# Brians_test_board_1_17.net
KiCad netlist of a schematic drawn in EAGLE
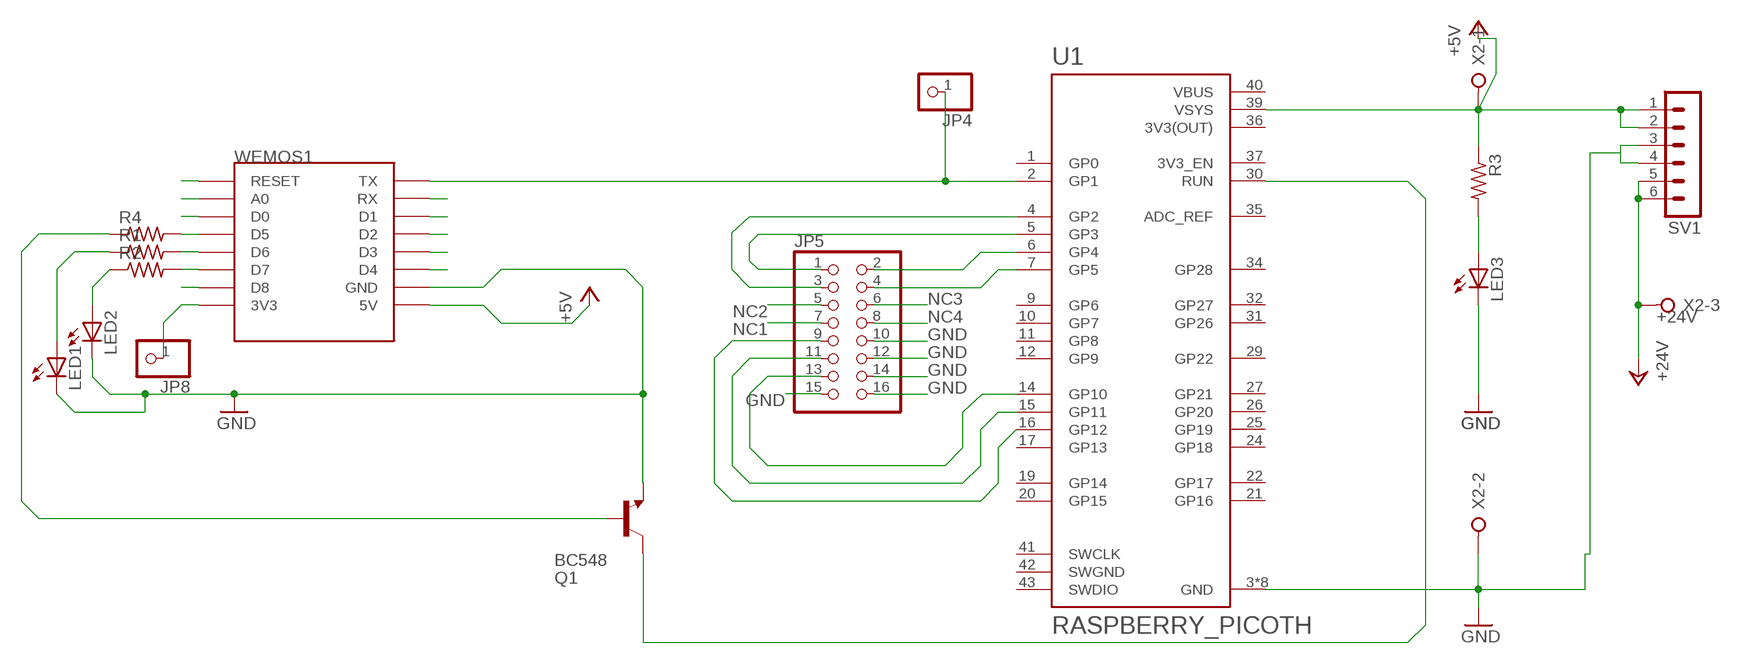
[diagram p0: schematic, sheet 1]

(export (version "E")
  (design (tool "Eeschema 10.0.6"))
  (components
    (comp (ref "JP4")
      (value "PINHD-1X1")
      (footprint "eagle-import:1X01")
      (libsource (lib "eagle-import") (part "PINHD-1X1"))
    )
    (comp (ref "JP5")
      (value "PINHD-2X8")
      (footprint "eagle-import:2X08")
      (libsource (lib "eagle-import") (part "PINHD-2X8"))
    )
    (comp (ref "JP8")
      (value "PINHD-1X1")
      (footprint "eagle-import:1X01")
      (libsource (lib "eagle-import") (part "PINHD-1X1"))
    )
    (comp (ref "LED1")
      (value "LED3MM")
      (footprint "eagle-import:LED3MM")
      (libsource (lib "eagle-import") (part "LED3MM"))
    )
    (comp (ref "LED2")
      (value "LED3MM")
      (footprint "eagle-import:LED3MM")
      (libsource (lib "eagle-import") (part "LED3MM"))
    )
    (comp (ref "LED3")
      (value "LED3MM")
      (footprint "eagle-import:LED3MM")
      (libsource (lib "eagle-import") (part "LED3MM"))
    )
    (comp (ref "Q1")
      (value "BC548")
      (footprint "eagle-import:TO92-EBC")
      (libsource (lib "eagle-import") (part "BC548"))
    )
    (comp (ref "R1")
      (value "R-US_0204/2V")
      (footprint "eagle-import:0204V")
      (libsource (lib "eagle-import") (part "R-US_0204/2V"))
    )
    (comp (ref "R2")
      (value "R-US_0204/2V")
      (footprint "eagle-import:0204V")
      (libsource (lib "eagle-import") (part "R-US_0204/2V"))
    )
    (comp (ref "R3")
      (value "R-US_0207/10")
      (footprint "eagle-import:0207_10")
      (libsource (lib "eagle-import") (part "R-US_0207/10"))
    )
    (comp (ref "R4")
      (value "R-US_0204/2V")
      (footprint "eagle-import:0204V")
      (libsource (lib "eagle-import") (part "R-US_0204/2V"))
    )
    (comp (ref "SV1")
      (value "MA06-1")
      (footprint "eagle-import:MA06-1")
      (libsource (lib "eagle-import") (part "MA06-1"))
    )
    (comp (ref "U1")
      (value "RASPBERRY_PICOTH")
      (footprint "eagle-import:PICO-PKG-TH")
      (libsource (lib "eagle-import") (part "RASPBERRY_PICOTH"))
    )
    (comp (ref "WEMOS1")
      (value "WEMOS-D1-MINI")
      (footprint "eagle-import:WEMOS-D1-MINI")
      (libsource (lib "eagle-import") (part "WEMOS-D1-MINI"))
    )
    (comp (ref "X2")
      (value "W237-3E")
      (footprint "eagle-import:W237-3E")
      (libsource (lib "eagle-import") (part "W237-3E"))
    )
  )
  (nets
    (net (code "1") (name "+5V") (class "Default")
      (node (ref "R3") (pin "1") (pinfunction "1_1") (pintype "passive"))
      (node (ref "SV1") (pin "1") (pinfunction "1_1") (pintype "passive"))
      (node (ref "SV1") (pin "2") (pinfunction "2_2") (pintype "passive"))
      (node (ref "U1") (pin "39") (pinfunction "VSYS_39") (pintype "power_in"))
      (node (ref "WEMOS1") (pin "5V") (pinfunction "5V_5V") (pintype "bidirectional"))
      (node (ref "X2") (pin "1") (pinfunction "KL_1") (pintype "passive"))
    )
    (net (code "2") (name "+24V") (class "Default")
      (node (ref "SV1") (pin "5") (pinfunction "5_5") (pintype "passive"))
      (node (ref "SV1") (pin "6") (pinfunction "6_6") (pintype "passive"))
      (node (ref "X2") (pin "3") (pinfunction "KL_3") (pintype "passive"))
    )
    (net (code "3") (name "/3V3(OUT)") (class "Default")
      (node (ref "U1") (pin "36") (pinfunction "3V3(OUT)_36") (pintype "power_in"))
    )
    (net (code "4") (name "/NC1") (class "Default")
      (node (ref "JP5") (pin "7") (pinfunction "7_7") (pintype "passive"))
    )
    (net (code "5") (name "/NC2") (class "Default")
      (node (ref "JP5") (pin "5") (pinfunction "5_5") (pintype "passive"))
    )
    (net (code "6") (name "/NC3") (class "Default")
      (node (ref "JP5") (pin "6") (pinfunction "6_6") (pintype "passive"))
    )
    (net (code "7") (name "/NC4") (class "Default")
      (node (ref "JP5") (pin "8") (pinfunction "8_8") (pintype "passive"))
    )
    (net (code "8") (name "/SWGND") (class "Default")
      (node (ref "U1") (pin "42") (pinfunction "SWGND_42") (pintype "power_in"))
    )
    (net (code "9") (name "/VBUS") (class "Default")
      (node (ref "U1") (pin "40") (pinfunction "VBUS_40") (pintype "power_in"))
    )
    (net (code "10") (name "GND") (class "Default")
      (node (ref "JP5") (pin "10") (pinfunction "10_10") (pintype "passive"))
      (node (ref "JP5") (pin "12") (pinfunction "12_12") (pintype "passive"))
      (node (ref "JP5") (pin "14") (pinfunction "14_14") (pintype "passive"))
      (node (ref "JP5") (pin "15") (pinfunction "15_15") (pintype "passive"))
      (node (ref "JP5") (pin "16") (pinfunction "16_16") (pintype "passive"))
      (node (ref "LED1") (pin "K") (pinfunction "C_K") (pintype "passive"))
      (node (ref "LED2") (pin "K") (pinfunction "C_K") (pintype "passive"))
      (node (ref "LED3") (pin "K") (pinfunction "C_K") (pintype "passive"))
      (node (ref "Q1") (pin "E") (pinfunction "E_E") (pintype "passive"))
      (node (ref "SV1") (pin "3") (pinfunction "3_3") (pintype "passive"))
      (node (ref "SV1") (pin "4") (pinfunction "4_4") (pintype "passive"))
      (node (ref "U1") (pin "13") (pinfunction "GND_13") (pintype "power_in"))
      (node (ref "U1") (pin "18") (pinfunction "GND_18") (pintype "power_in"))
      (node (ref "U1") (pin "23") (pinfunction "GND_23") (pintype "power_in"))
      (node (ref "U1") (pin "28") (pinfunction "GND_28") (pintype "power_in"))
      (node (ref "U1") (pin "3") (pinfunction "GND_3") (pintype "power_in"))
      (node (ref "U1") (pin "33") (pinfunction "GND_33") (pintype "power_in"))
      (node (ref "U1") (pin "38") (pinfunction "GND_38") (pintype "power_in"))
      (node (ref "U1") (pin "8") (pinfunction "GND_8") (pintype "power_in"))
      (node (ref "WEMOS1") (pin "GND") (pinfunction "GND_GND") (pintype "bidirectional"))
      (node (ref "X2") (pin "2") (pinfunction "KL_2") (pintype "passive"))
    )
    (net (code "11") (name "Net-(JP8-Pad1)") (class "Default")
      (node (ref "JP8") (pin "1") (pinfunction "1_1") (pintype "passive"))
      (node (ref "WEMOS1") (pin "3V3") (pinfunction "3V3_3V3") (pintype "bidirectional"))
    )
    (net (code "12") (name "Net-(LED1-PadA)") (class "Default")
      (node (ref "LED1") (pin "A") (pinfunction "A_A") (pintype "passive"))
      (node (ref "R1") (pin "1") (pinfunction "1_1") (pintype "passive"))
    )
    (net (code "13") (name "Net-(LED2-PadA)") (class "Default")
      (node (ref "LED2") (pin "A") (pinfunction "A_A") (pintype "passive"))
      (node (ref "R2") (pin "1") (pinfunction "1_1") (pintype "passive"))
    )
    (net (code "14") (name "Net-(LED3-PadA)") (class "Default")
      (node (ref "LED3") (pin "A") (pinfunction "A_A") (pintype "passive"))
      (node (ref "R3") (pin "2") (pinfunction "2_2") (pintype "passive"))
    )
    (net (code "15") (name "Net-(Q1-PadB)") (class "Default")
      (node (ref "Q1") (pin "B") (pinfunction "B_B") (pintype "passive"))
      (node (ref "R4") (pin "1") (pinfunction "1_1") (pintype "passive"))
    )
    (net (code "16") (name "Net-(R1-Pad2)") (class "Default")
      (node (ref "R1") (pin "2") (pinfunction "2_2") (pintype "passive"))
      (node (ref "WEMOS1") (pin "D6") (pinfunction "D6_D6") (pintype "bidirectional"))
    )
    (net (code "17") (name "Net-(R2-Pad2)") (class "Default")
      (node (ref "R2") (pin "2") (pinfunction "2_2") (pintype "passive"))
      (node (ref "WEMOS1") (pin "D7") (pinfunction "D7_D7") (pintype "bidirectional"))
    )
    (net (code "18") (name "Net-(R4-Pad2)") (class "Default")
      (node (ref "R4") (pin "2") (pinfunction "2_2") (pintype "passive"))
      (node (ref "WEMOS1") (pin "D5") (pinfunction "D5_D5") (pintype "bidirectional"))
    )
    (net (code "19") (name "Net-(U1-GP1)") (class "Default")
      (node (ref "JP4") (pin "1") (pinfunction "1_1") (pintype "passive"))
      (node (ref "U1") (pin "2") (pinfunction "GP1_2") (pintype "bidirectional"))
      (node (ref "WEMOS1") (pin "TX") (pinfunction "TX_TX") (pintype "bidirectional"))
    )
    (net (code "20") (name "Net-(U1-GP2)") (class "Default")
      (node (ref "JP5") (pin "3") (pinfunction "3_3") (pintype "passive"))
      (node (ref "U1") (pin "4") (pinfunction "GP2_4") (pintype "bidirectional"))
    )
    (net (code "21") (name "Net-(U1-GP3)") (class "Default")
      (node (ref "JP5") (pin "1") (pinfunction "1_1") (pintype "passive"))
      (node (ref "U1") (pin "5") (pinfunction "GP3_5") (pintype "bidirectional"))
    )
    (net (code "22") (name "Net-(U1-GP4)") (class "Default")
      (node (ref "JP5") (pin "2") (pinfunction "2_2") (pintype "passive"))
      (node (ref "U1") (pin "6") (pinfunction "GP4_6") (pintype "bidirectional"))
    )
    (net (code "23") (name "Net-(U1-GP5)") (class "Default")
      (node (ref "JP5") (pin "4") (pinfunction "4_4") (pintype "passive"))
      (node (ref "U1") (pin "7") (pinfunction "GP5_7") (pintype "bidirectional"))
    )
    (net (code "24") (name "Net-(U1-GP10)") (class "Default")
      (node (ref "JP5") (pin "13") (pinfunction "13_13") (pintype "passive"))
      (node (ref "U1") (pin "14") (pinfunction "GP10_14") (pintype "bidirectional"))
    )
    (net (code "25") (name "Net-(U1-GP11)") (class "Default")
      (node (ref "JP5") (pin "11") (pinfunction "11_11") (pintype "passive"))
      (node (ref "U1") (pin "15") (pinfunction "GP11_15") (pintype "bidirectional"))
    )
    (net (code "26") (name "Net-(U1-GP12)") (class "Default")
      (node (ref "JP5") (pin "9") (pinfunction "9_9") (pintype "passive"))
      (node (ref "U1") (pin "16") (pinfunction "GP12_16") (pintype "bidirectional"))
    )
    (net (code "27") (name "Net-(U1-RUN)") (class "Default")
      (node (ref "Q1") (pin "C") (pinfunction "C_C") (pintype "passive"))
      (node (ref "U1") (pin "30") (pinfunction "RUN_30") (pintype "input"))
    )
    (net (code "28") (name "unconnected-(U1-3V3_EN-Pad37)") (class "Default")
      (node (ref "U1") (pin "37") (pinfunction "3V3_EN_37") (pintype "input"))
    )
    (net (code "29") (name "unconnected-(U1-ADC_REF-Pad35)") (class "Default")
      (node (ref "U1") (pin "35") (pinfunction "ADC_REF_35") (pintype "input"))
    )
    (net (code "30") (name "unconnected-(U1-GP0-Pad1)") (class "Default")
      (node (ref "U1") (pin "1") (pinfunction "GP0_1") (pintype "bidirectional"))
    )
    (net (code "31") (name "unconnected-(U1-GP6-Pad9)") (class "Default")
      (node (ref "U1") (pin "9") (pinfunction "GP6_9") (pintype "bidirectional"))
    )
    (net (code "32") (name "unconnected-(U1-GP7-Pad10)") (class "Default")
      (node (ref "U1") (pin "10") (pinfunction "GP7_10") (pintype "bidirectional"))
    )
    (net (code "33") (name "unconnected-(U1-GP8-Pad11)") (class "Default")
      (node (ref "U1") (pin "11") (pinfunction "GP8_11") (pintype "bidirectional"))
    )
    (net (code "34") (name "unconnected-(U1-GP9-Pad12)") (class "Default")
      (node (ref "U1") (pin "12") (pinfunction "GP9_12") (pintype "bidirectional"))
    )
    (net (code "35") (name "unconnected-(U1-GP13-Pad17)") (class "Default")
      (node (ref "U1") (pin "17") (pinfunction "GP13_17") (pintype "bidirectional"))
    )
    (net (code "36") (name "unconnected-(U1-GP14-Pad19)") (class "Default")
      (node (ref "U1") (pin "19") (pinfunction "GP14_19") (pintype "bidirectional"))
    )
    (net (code "37") (name "unconnected-(U1-GP15-Pad20)") (class "Default")
      (node (ref "U1") (pin "20") (pinfunction "GP15_20") (pintype "bidirectional"))
    )
    (net (code "38") (name "unconnected-(U1-GP16-Pad21)") (class "Default")
      (node (ref "U1") (pin "21") (pinfunction "GP16_21") (pintype "bidirectional"))
    )
    (net (code "39") (name "unconnected-(U1-GP17-Pad22)") (class "Default")
      (node (ref "U1") (pin "22") (pinfunction "GP17_22") (pintype "bidirectional"))
    )
    (net (code "40") (name "unconnected-(U1-GP18-Pad24)") (class "Default")
      (node (ref "U1") (pin "24") (pinfunction "GP18_24") (pintype "bidirectional"))
    )
    (net (code "41") (name "unconnected-(U1-GP19-Pad25)") (class "Default")
      (node (ref "U1") (pin "25") (pinfunction "GP19_25") (pintype "bidirectional"))
    )
    (net (code "42") (name "unconnected-(U1-GP20-Pad26)") (class "Default")
      (node (ref "U1") (pin "26") (pinfunction "GP20_26") (pintype "bidirectional"))
    )
    (net (code "43") (name "unconnected-(U1-GP21-Pad27)") (class "Default")
      (node (ref "U1") (pin "27") (pinfunction "GP21_27") (pintype "bidirectional"))
    )
    (net (code "44") (name "unconnected-(U1-GP22-Pad29)") (class "Default")
      (node (ref "U1") (pin "29") (pinfunction "GP22_29") (pintype "bidirectional"))
    )
    (net (code "45") (name "unconnected-(U1-GP26-Pad31)") (class "Default")
      (node (ref "U1") (pin "31") (pinfunction "GP26_31") (pintype "bidirectional"))
    )
    (net (code "46") (name "unconnected-(U1-GP27-Pad32)") (class "Default")
      (node (ref "U1") (pin "32") (pinfunction "GP27_32") (pintype "bidirectional"))
    )
    (net (code "47") (name "unconnected-(U1-GP28-Pad34)") (class "Default")
      (node (ref "U1") (pin "34") (pinfunction "GP28_34") (pintype "bidirectional"))
    )
    (net (code "48") (name "unconnected-(U1-SWCLK-Pad41)") (class "Default")
      (node (ref "U1") (pin "41") (pinfunction "SWCLK_41") (pintype "input"))
    )
    (net (code "49") (name "unconnected-(U1-SWDIO-Pad43)") (class "Default")
      (node (ref "U1") (pin "43") (pinfunction "SWDIO_43") (pintype "bidirectional"))
    )
    (net (code "50") (name "unconnected-(WEMOS1-PadA0)") (class "Default")
      (node (ref "WEMOS1") (pin "A0") (pinfunction "A0_A0") (pintype "bidirectional"))
    )
    (net (code "51") (name "unconnected-(WEMOS1-PadD0)") (class "Default")
      (node (ref "WEMOS1") (pin "D0") (pinfunction "D0_D0") (pintype "bidirectional"))
    )
    (net (code "52") (name "unconnected-(WEMOS1-PadD1)") (class "Default")
      (node (ref "WEMOS1") (pin "D1") (pinfunction "D1_D1") (pintype "bidirectional"))
    )
    (net (code "53") (name "unconnected-(WEMOS1-PadD2)") (class "Default")
      (node (ref "WEMOS1") (pin "D2") (pinfunction "D2_D2") (pintype "bidirectional"))
    )
    (net (code "54") (name "unconnected-(WEMOS1-PadD3)") (class "Default")
      (node (ref "WEMOS1") (pin "D3") (pinfunction "D3_D3") (pintype "bidirectional"))
    )
    (net (code "55") (name "unconnected-(WEMOS1-PadD4)") (class "Default")
      (node (ref "WEMOS1") (pin "D4") (pinfunction "D4_D4") (pintype "bidirectional"))
    )
    (net (code "56") (name "unconnected-(WEMOS1-PadD8)") (class "Default")
      (node (ref "WEMOS1") (pin "D8") (pinfunction "D8_D8") (pintype "bidirectional"))
    )
    (net (code "57") (name "unconnected-(WEMOS1-PadRESET)") (class "Default")
      (node (ref "WEMOS1") (pin "RESET") (pinfunction "RESET_RESET") (pintype "bidirectional"))
    )
    (net (code "58") (name "unconnected-(WEMOS1-PadRX)") (class "Default")
      (node (ref "WEMOS1") (pin "RX") (pinfunction "RX_RX") (pintype "bidirectional"))
    )
  )
)
